# STM32Headers.net
KiCad netlist of a schematic drawn in Altium Designer
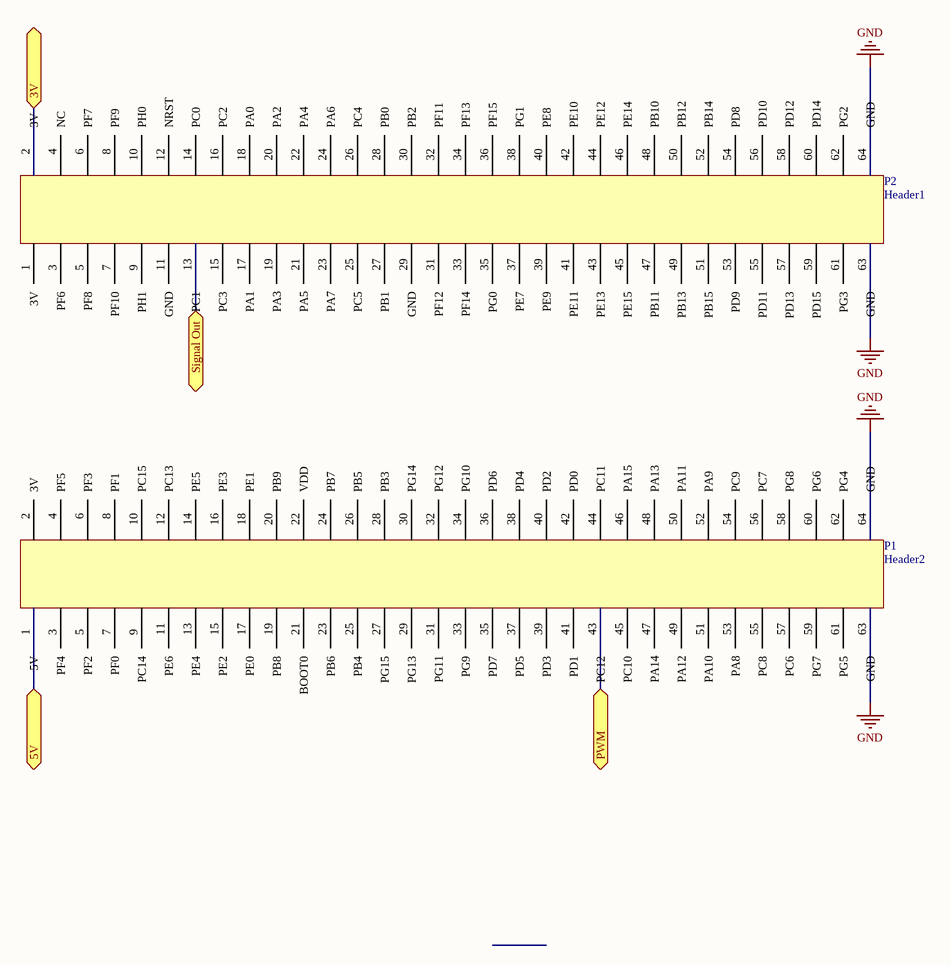
[diagram p0: STM32Headers.SchDoc]

(export (version "E")
  (design (tool "Eeschema 10.0.6"))
  (components
    (comp (ref "P1")
      (value "Header2")
      (footprint "STM32F4DiscoHeader")
      (libsource (lib "STM32F4DISCOHEAD2") (part "Component_1"))
    )
    (comp (ref "P2")
      (value "Header1")
      (footprint "STM32F4DiscoHeader")
      (description "Header for STM32F429 pinout")
      (libsource (lib "STM32F4DISCOHEAD") (part "Component_1"))
    )
  )
  (nets
    (net (code "1") (name "/3V") (class "Default")
      (node (ref "P2") (pin "2") (pinfunction "3V_2") (pintype "power_in"))
    )
    (net (code "2") (name "/5V") (class "Default")
      (node (ref "P1") (pin "1") (pinfunction "5V_1") (pintype "power_in"))
    )
    (net (code "3") (name "/PWM") (class "Default")
      (node (ref "P1") (pin "43") (pinfunction "PC12_43") (pintype "passive"))
    )
    (net (code "4") (name "/Signal Out") (class "Default")
      (node (ref "P2") (pin "13") (pinfunction "PC1_13") (pintype "passive"))
    )
    (net (code "5") (name "GND") (class "Default")
      (node (ref "P1") (pin "63") (pinfunction "GND_63") (pintype "power_in"))
      (node (ref "P1") (pin "64") (pinfunction "GND_64") (pintype "power_in"))
      (node (ref "P2") (pin "63") (pinfunction "GND_63") (pintype "power_in"))
      (node (ref "P2") (pin "64") (pinfunction "GND_64") (pintype "power_in"))
    )
    (net (code "6") (name "unconnected-(P1-3V-Pad2)") (class "Default")
      (node (ref "P1") (pin "2") (pinfunction "3V_2") (pintype "power_in"))
    )
    (net (code "7") (name "unconnected-(P1-BOOT0-Pad21)") (class "Default")
      (node (ref "P1") (pin "21") (pinfunction "BOOT0_21") (pintype "passive"))
    )
    (net (code "8") (name "unconnected-(P1-PA8-Pad53)") (class "Default")
      (node (ref "P1") (pin "53") (pinfunction "PA8_53") (pintype "passive"))
    )
    (net (code "9") (name "unconnected-(P1-PA9-Pad52)") (class "Default")
      (node (ref "P1") (pin "52") (pinfunction "PA9_52") (pintype "passive"))
    )
    (net (code "10") (name "unconnected-(P1-PA10-Pad51)") (class "Default")
      (node (ref "P1") (pin "51") (pinfunction "PA10_51") (pintype "passive"))
    )
    (net (code "11") (name "unconnected-(P1-PA11-Pad50)") (class "Default")
      (node (ref "P1") (pin "50") (pinfunction "PA11_50") (pintype "passive"))
    )
    (net (code "12") (name "unconnected-(P1-PA12-Pad49)") (class "Default")
      (node (ref "P1") (pin "49") (pinfunction "PA12_49") (pintype "passive"))
    )
    (net (code "13") (name "unconnected-(P1-PA13-Pad48)") (class "Default")
      (node (ref "P1") (pin "48") (pinfunction "PA13_48") (pintype "passive"))
    )
    (net (code "14") (name "unconnected-(P1-PA14-Pad47)") (class "Default")
      (node (ref "P1") (pin "47") (pinfunction "PA14_47") (pintype "passive"))
    )
    (net (code "15") (name "unconnected-(P1-PA15-Pad46)") (class "Default")
      (node (ref "P1") (pin "46") (pinfunction "PA15_46") (pintype "passive"))
    )
    (net (code "16") (name "unconnected-(P1-PB3-Pad28)") (class "Default")
      (node (ref "P1") (pin "28") (pinfunction "PB3_28") (pintype "passive"))
    )
    (net (code "17") (name "unconnected-(P1-PB4-Pad25)") (class "Default")
      (node (ref "P1") (pin "25") (pinfunction "PB4_25") (pintype "passive"))
    )
    (net (code "18") (name "unconnected-(P1-PB5-Pad26)") (class "Default")
      (node (ref "P1") (pin "26") (pinfunction "PB5_26") (pintype "passive"))
    )
    (net (code "19") (name "unconnected-(P1-PB6-Pad23)") (class "Default")
      (node (ref "P1") (pin "23") (pinfunction "PB6_23") (pintype "passive"))
    )
    (net (code "20") (name "unconnected-(P1-PB7-Pad24)") (class "Default")
      (node (ref "P1") (pin "24") (pinfunction "PB7_24") (pintype "passive"))
    )
    (net (code "21") (name "unconnected-(P1-PB8-Pad19)") (class "Default")
      (node (ref "P1") (pin "19") (pinfunction "PB8_19") (pintype "passive"))
    )
    (net (code "22") (name "unconnected-(P1-PB9-Pad20)") (class "Default")
      (node (ref "P1") (pin "20") (pinfunction "PB9_20") (pintype "passive"))
    )
    (net (code "23") (name "unconnected-(P1-PC6-Pad57)") (class "Default")
      (node (ref "P1") (pin "57") (pinfunction "PC6_57") (pintype "passive"))
    )
    (net (code "24") (name "unconnected-(P1-PC7-Pad56)") (class "Default")
      (node (ref "P1") (pin "56") (pinfunction "PC7_56") (pintype "passive"))
    )
    (net (code "25") (name "unconnected-(P1-PC8-Pad55)") (class "Default")
      (node (ref "P1") (pin "55") (pinfunction "PC8_55") (pintype "passive"))
    )
    (net (code "26") (name "unconnected-(P1-PC9-Pad54)") (class "Default")
      (node (ref "P1") (pin "54") (pinfunction "PC9_54") (pintype "passive"))
    )
    (net (code "27") (name "unconnected-(P1-PC10-Pad45)") (class "Default")
      (node (ref "P1") (pin "45") (pinfunction "PC10_45") (pintype "passive"))
    )
    (net (code "28") (name "unconnected-(P1-PC11-Pad44)") (class "Default")
      (node (ref "P1") (pin "44") (pinfunction "PC11_44") (pintype "passive"))
    )
    (net (code "29") (name "unconnected-(P1-PC13-Pad12)") (class "Default")
      (node (ref "P1") (pin "12") (pinfunction "PC13_12") (pintype "passive"))
    )
    (net (code "30") (name "unconnected-(P1-PC14-Pad9)") (class "Default")
      (node (ref "P1") (pin "9") (pinfunction "PC14_9") (pintype "passive"))
    )
    (net (code "31") (name "unconnected-(P1-PC15-Pad10)") (class "Default")
      (node (ref "P1") (pin "10") (pinfunction "PC15_10") (pintype "passive"))
    )
    (net (code "32") (name "unconnected-(P1-PD0-Pad42)") (class "Default")
      (node (ref "P1") (pin "42") (pinfunction "PD0_42") (pintype "passive"))
    )
    (net (code "33") (name "unconnected-(P1-PD1-Pad41)") (class "Default")
      (node (ref "P1") (pin "41") (pinfunction "PD1_41") (pintype "passive"))
    )
    (net (code "34") (name "unconnected-(P1-PD2-Pad40)") (class "Default")
      (node (ref "P1") (pin "40") (pinfunction "PD2_40") (pintype "passive"))
    )
    (net (code "35") (name "unconnected-(P1-PD3-Pad39)") (class "Default")
      (node (ref "P1") (pin "39") (pinfunction "PD3_39") (pintype "passive"))
    )
    (net (code "36") (name "unconnected-(P1-PD4-Pad38)") (class "Default")
      (node (ref "P1") (pin "38") (pinfunction "PD4_38") (pintype "passive"))
    )
    (net (code "37") (name "unconnected-(P1-PD5-Pad37)") (class "Default")
      (node (ref "P1") (pin "37") (pinfunction "PD5_37") (pintype "passive"))
    )
    (net (code "38") (name "unconnected-(P1-PD6-Pad36)") (class "Default")
      (node (ref "P1") (pin "36") (pinfunction "PD6_36") (pintype "passive"))
    )
    (net (code "39") (name "unconnected-(P1-PD7-Pad35)") (class "Default")
      (node (ref "P1") (pin "35") (pinfunction "PD7_35") (pintype "passive"))
    )
    (net (code "40") (name "unconnected-(P1-PE0-Pad17)") (class "Default")
      (node (ref "P1") (pin "17") (pinfunction "PE0_17") (pintype "passive"))
    )
    (net (code "41") (name "unconnected-(P1-PE1-Pad18)") (class "Default")
      (node (ref "P1") (pin "18") (pinfunction "PE1_18") (pintype "passive"))
    )
    (net (code "42") (name "unconnected-(P1-PE2-Pad15)") (class "Default")
      (node (ref "P1") (pin "15") (pinfunction "PE2_15") (pintype "passive"))
    )
    (net (code "43") (name "unconnected-(P1-PE3-Pad16)") (class "Default")
      (node (ref "P1") (pin "16") (pinfunction "PE3_16") (pintype "passive"))
    )
    (net (code "44") (name "unconnected-(P1-PE4-Pad13)") (class "Default")
      (node (ref "P1") (pin "13") (pinfunction "PE4_13") (pintype "passive"))
    )
    (net (code "45") (name "unconnected-(P1-PE5-Pad14)") (class "Default")
      (node (ref "P1") (pin "14") (pinfunction "PE5_14") (pintype "passive"))
    )
    (net (code "46") (name "unconnected-(P1-PE6-Pad11)") (class "Default")
      (node (ref "P1") (pin "11") (pinfunction "PE6_11") (pintype "passive"))
    )
    (net (code "47") (name "unconnected-(P1-PF0-Pad7)") (class "Default")
      (node (ref "P1") (pin "7") (pinfunction "PF0_7") (pintype "passive"))
    )
    (net (code "48") (name "unconnected-(P1-PF1-Pad8)") (class "Default")
      (node (ref "P1") (pin "8") (pinfunction "PF1_8") (pintype "passive"))
    )
    (net (code "49") (name "unconnected-(P1-PF2-Pad5)") (class "Default")
      (node (ref "P1") (pin "5") (pinfunction "PF2_5") (pintype "passive"))
    )
    (net (code "50") (name "unconnected-(P1-PF3-Pad6)") (class "Default")
      (node (ref "P1") (pin "6") (pinfunction "PF3_6") (pintype "passive"))
    )
    (net (code "51") (name "unconnected-(P1-PF4-Pad3)") (class "Default")
      (node (ref "P1") (pin "3") (pinfunction "PF4_3") (pintype "passive"))
    )
    (net (code "52") (name "unconnected-(P1-PF5-Pad4)") (class "Default")
      (node (ref "P1") (pin "4") (pinfunction "PF5_4") (pintype "passive"))
    )
    (net (code "53") (name "unconnected-(P1-PG4-Pad62)") (class "Default")
      (node (ref "P1") (pin "62") (pinfunction "PG4_62") (pintype "passive"))
    )
    (net (code "54") (name "unconnected-(P1-PG5-Pad61)") (class "Default")
      (node (ref "P1") (pin "61") (pinfunction "PG5_61") (pintype "passive"))
    )
    (net (code "55") (name "unconnected-(P1-PG6-Pad60)") (class "Default")
      (node (ref "P1") (pin "60") (pinfunction "PG6_60") (pintype "passive"))
    )
    (net (code "56") (name "unconnected-(P1-PG7-Pad59)") (class "Default")
      (node (ref "P1") (pin "59") (pinfunction "PG7_59") (pintype "passive"))
    )
    (net (code "57") (name "unconnected-(P1-PG8-Pad58)") (class "Default")
      (node (ref "P1") (pin "58") (pinfunction "PG8_58") (pintype "passive"))
    )
    (net (code "58") (name "unconnected-(P1-PG9-Pad33)") (class "Default")
      (node (ref "P1") (pin "33") (pinfunction "PG9_33") (pintype "passive"))
    )
    (net (code "59") (name "unconnected-(P1-PG10-Pad34)") (class "Default")
      (node (ref "P1") (pin "34") (pinfunction "PG10_34") (pintype "passive"))
    )
    (net (code "60") (name "unconnected-(P1-PG11-Pad31)") (class "Default")
      (node (ref "P1") (pin "31") (pinfunction "PG11_31") (pintype "passive"))
    )
    (net (code "61") (name "unconnected-(P1-PG12-Pad32)") (class "Default")
      (node (ref "P1") (pin "32") (pinfunction "PG12_32") (pintype "passive"))
    )
    (net (code "62") (name "unconnected-(P1-PG13-Pad29)") (class "Default")
      (node (ref "P1") (pin "29") (pinfunction "PG13_29") (pintype "passive"))
    )
    (net (code "63") (name "unconnected-(P1-PG14-Pad30)") (class "Default")
      (node (ref "P1") (pin "30") (pinfunction "PG14_30") (pintype "passive"))
    )
    (net (code "64") (name "unconnected-(P1-PG15-Pad27)") (class "Default")
      (node (ref "P1") (pin "27") (pinfunction "PG15_27") (pintype "passive"))
    )
    (net (code "65") (name "unconnected-(P1-VDD-Pad22)") (class "Default")
      (node (ref "P1") (pin "22") (pinfunction "VDD_22") (pintype "power_in"))
    )
    (net (code "66") (name "unconnected-(P2-3V-Pad1)") (class "Default")
      (node (ref "P2") (pin "1") (pinfunction "3V_1") (pintype "power_in"))
    )
    (net (code "67") (name "unconnected-(P2-GND-Pad11)") (class "Default")
      (node (ref "P2") (pin "11") (pinfunction "GND_11") (pintype "power_in"))
    )
    (net (code "68") (name "unconnected-(P2-GND-Pad29)") (class "Default")
      (node (ref "P2") (pin "29") (pinfunction "GND_29") (pintype "power_in"))
    )
    (net (code "69") (name "unconnected-(P2-NC-Pad4)") (class "Default")
      (node (ref "P2") (pin "4") (pinfunction "NC_4") (pintype "passive"))
    )
    (net (code "70") (name "unconnected-(P2-NRST-Pad12)") (class "Default")
      (node (ref "P2") (pin "12") (pinfunction "NRST_12") (pintype "passive"))
    )
    (net (code "71") (name "unconnected-(P2-PA0-Pad18)") (class "Default")
      (node (ref "P2") (pin "18") (pinfunction "PA0_18") (pintype "passive"))
    )
    (net (code "72") (name "unconnected-(P2-PA1-Pad17)") (class "Default")
      (node (ref "P2") (pin "17") (pinfunction "PA1_17") (pintype "passive"))
    )
    (net (code "73") (name "unconnected-(P2-PA2-Pad20)") (class "Default")
      (node (ref "P2") (pin "20") (pinfunction "PA2_20") (pintype "passive"))
    )
    (net (code "74") (name "unconnected-(P2-PA3-Pad19)") (class "Default")
      (node (ref "P2") (pin "19") (pinfunction "PA3_19") (pintype "passive"))
    )
    (net (code "75") (name "unconnected-(P2-PA4-Pad22)") (class "Default")
      (node (ref "P2") (pin "22") (pinfunction "PA4_22") (pintype "passive"))
    )
    (net (code "76") (name "unconnected-(P2-PA5-Pad21)") (class "Default")
      (node (ref "P2") (pin "21") (pinfunction "PA5_21") (pintype "passive"))
    )
    (net (code "77") (name "unconnected-(P2-PA6-Pad24)") (class "Default")
      (node (ref "P2") (pin "24") (pinfunction "PA6_24") (pintype "passive"))
    )
    (net (code "78") (name "unconnected-(P2-PA7-Pad23)") (class "Default")
      (node (ref "P2") (pin "23") (pinfunction "PA7_23") (pintype "passive"))
    )
    (net (code "79") (name "unconnected-(P2-PB0-Pad28)") (class "Default")
      (node (ref "P2") (pin "28") (pinfunction "PB0_28") (pintype "passive"))
    )
    (net (code "80") (name "unconnected-(P2-PB1-Pad27)") (class "Default")
      (node (ref "P2") (pin "27") (pinfunction "PB1_27") (pintype "passive"))
    )
    (net (code "81") (name "unconnected-(P2-PB2-Pad30)") (class "Default")
      (node (ref "P2") (pin "30") (pinfunction "PB2_30") (pintype "passive"))
    )
    (net (code "82") (name "unconnected-(P2-PB10-Pad48)") (class "Default")
      (node (ref "P2") (pin "48") (pinfunction "PB10_48") (pintype "passive"))
    )
    (net (code "83") (name "unconnected-(P2-PB11-Pad47)") (class "Default")
      (node (ref "P2") (pin "47") (pinfunction "PB11_47") (pintype "passive"))
    )
    (net (code "84") (name "unconnected-(P2-PB12-Pad50)") (class "Default")
      (node (ref "P2") (pin "50") (pinfunction "PB12_50") (pintype "passive"))
    )
    (net (code "85") (name "unconnected-(P2-PB13-Pad49)") (class "Default")
      (node (ref "P2") (pin "49") (pinfunction "PB13_49") (pintype "passive"))
    )
    (net (code "86") (name "unconnected-(P2-PB14-Pad52)") (class "Default")
      (node (ref "P2") (pin "52") (pinfunction "PB14_52") (pintype "passive"))
    )
    (net (code "87") (name "unconnected-(P2-PB15-Pad51)") (class "Default")
      (node (ref "P2") (pin "51") (pinfunction "PB15_51") (pintype "passive"))
    )
    (net (code "88") (name "unconnected-(P2-PC0-Pad14)") (class "Default")
      (node (ref "P2") (pin "14") (pinfunction "PC0_14") (pintype "passive"))
    )
    (net (code "89") (name "unconnected-(P2-PC2-Pad16)") (class "Default")
      (node (ref "P2") (pin "16") (pinfunction "PC2_16") (pintype "passive"))
    )
    (net (code "90") (name "unconnected-(P2-PC3-Pad15)") (class "Default")
      (node (ref "P2") (pin "15") (pinfunction "PC3_15") (pintype "passive"))
    )
    (net (code "91") (name "unconnected-(P2-PC4-Pad26)") (class "Default")
      (node (ref "P2") (pin "26") (pinfunction "PC4_26") (pintype "passive"))
    )
    (net (code "92") (name "unconnected-(P2-PC5-Pad25)") (class "Default")
      (node (ref "P2") (pin "25") (pinfunction "PC5_25") (pintype "passive"))
    )
    (net (code "93") (name "unconnected-(P2-PD8-Pad54)") (class "Default")
      (node (ref "P2") (pin "54") (pinfunction "PD8_54") (pintype "passive"))
    )
    (net (code "94") (name "unconnected-(P2-PD9-Pad53)") (class "Default")
      (node (ref "P2") (pin "53") (pinfunction "PD9_53") (pintype "passive"))
    )
    (net (code "95") (name "unconnected-(P2-PD10-Pad56)") (class "Default")
      (node (ref "P2") (pin "56") (pinfunction "PD10_56") (pintype "passive"))
    )
    (net (code "96") (name "unconnected-(P2-PD11-Pad55)") (class "Default")
      (node (ref "P2") (pin "55") (pinfunction "PD11_55") (pintype "passive"))
    )
    (net (code "97") (name "unconnected-(P2-PD12-Pad58)") (class "Default")
      (node (ref "P2") (pin "58") (pinfunction "PD12_58") (pintype "passive"))
    )
    (net (code "98") (name "unconnected-(P2-PD13-Pad57)") (class "Default")
      (node (ref "P2") (pin "57") (pinfunction "PD13_57") (pintype "passive"))
    )
    (net (code "99") (name "unconnected-(P2-PD14-Pad60)") (class "Default")
      (node (ref "P2") (pin "60") (pinfunction "PD14_60") (pintype "passive"))
    )
    (net (code "100") (name "unconnected-(P2-PD15-Pad59)") (class "Default")
      (node (ref "P2") (pin "59") (pinfunction "PD15_59") (pintype "passive"))
    )
    (net (code "101") (name "unconnected-(P2-PE7-Pad37)") (class "Default")
      (node (ref "P2") (pin "37") (pinfunction "PE7_37") (pintype "passive"))
    )
    (net (code "102") (name "unconnected-(P2-PE8-Pad40)") (class "Default")
      (node (ref "P2") (pin "40") (pinfunction "PE8_40") (pintype "passive"))
    )
    (net (code "103") (name "unconnected-(P2-PE9-Pad39)") (class "Default")
      (node (ref "P2") (pin "39") (pinfunction "PE9_39") (pintype "passive"))
    )
    (net (code "104") (name "unconnected-(P2-PE10-Pad42)") (class "Default")
      (node (ref "P2") (pin "42") (pinfunction "PE10_42") (pintype "passive"))
    )
    (net (code "105") (name "unconnected-(P2-PE11-Pad41)") (class "Default")
      (node (ref "P2") (pin "41") (pinfunction "PE11_41") (pintype "passive"))
    )
    (net (code "106") (name "unconnected-(P2-PE12-Pad44)") (class "Default")
      (node (ref "P2") (pin "44") (pinfunction "PE12_44") (pintype "passive"))
    )
    (net (code "107") (name "unconnected-(P2-PE13-Pad43)") (class "Default")
      (node (ref "P2") (pin "43") (pinfunction "PE13_43") (pintype "passive"))
    )
    (net (code "108") (name "unconnected-(P2-PE14-Pad46)") (class "Default")
      (node (ref "P2") (pin "46") (pinfunction "PE14_46") (pintype "passive"))
    )
    (net (code "109") (name "unconnected-(P2-PE15-Pad45)") (class "Default")
      (node (ref "P2") (pin "45") (pinfunction "PE15_45") (pintype "passive"))
    )
    (net (code "110") (name "unconnected-(P2-PF6-Pad3)") (class "Default")
      (node (ref "P2") (pin "3") (pinfunction "PF6_3") (pintype "passive"))
    )
    (net (code "111") (name "unconnected-(P2-PF7-Pad6)") (class "Default")
      (node (ref "P2") (pin "6") (pinfunction "PF7_6") (pintype "passive"))
    )
    (net (code "112") (name "unconnected-(P2-PF8-Pad5)") (class "Default")
      (node (ref "P2") (pin "5") (pinfunction "PF8_5") (pintype "passive"))
    )
    (net (code "113") (name "unconnected-(P2-PF9-Pad8)") (class "Default")
      (node (ref "P2") (pin "8") (pinfunction "PF9_8") (pintype "passive"))
    )
    (net (code "114") (name "unconnected-(P2-PF10-Pad7)") (class "Default")
      (node (ref "P2") (pin "7") (pinfunction "PF10_7") (pintype "passive"))
    )
    (net (code "115") (name "unconnected-(P2-PF11-Pad32)") (class "Default")
      (node (ref "P2") (pin "32") (pinfunction "PF11_32") (pintype "passive"))
    )
    (net (code "116") (name "unconnected-(P2-PF12-Pad31)") (class "Default")
      (node (ref "P2") (pin "31") (pinfunction "PF12_31") (pintype "passive"))
    )
    (net (code "117") (name "unconnected-(P2-PF13-Pad34)") (class "Default")
      (node (ref "P2") (pin "34") (pinfunction "PF13_34") (pintype "passive"))
    )
    (net (code "118") (name "unconnected-(P2-PF14-Pad33)") (class "Default")
      (node (ref "P2") (pin "33") (pinfunction "PF14_33") (pintype "passive"))
    )
    (net (code "119") (name "unconnected-(P2-PF15-Pad36)") (class "Default")
      (node (ref "P2") (pin "36") (pinfunction "PF15_36") (pintype "passive"))
    )
    (net (code "120") (name "unconnected-(P2-PG0-Pad35)") (class "Default")
      (node (ref "P2") (pin "35") (pinfunction "PG0_35") (pintype "passive"))
    )
    (net (code "121") (name "unconnected-(P2-PG1-Pad38)") (class "Default")
      (node (ref "P2") (pin "38") (pinfunction "PG1_38") (pintype "passive"))
    )
    (net (code "122") (name "unconnected-(P2-PG2-Pad62)") (class "Default")
      (node (ref "P2") (pin "62") (pinfunction "PG2_62") (pintype "passive"))
    )
    (net (code "123") (name "unconnected-(P2-PG3-Pad61)") (class "Default")
      (node (ref "P2") (pin "61") (pinfunction "PG3_61") (pintype "passive"))
    )
    (net (code "124") (name "unconnected-(P2-PH0-Pad10)") (class "Default")
      (node (ref "P2") (pin "10") (pinfunction "PH0_10") (pintype "passive"))
    )
    (net (code "125") (name "unconnected-(P2-PH1-Pad9)") (class "Default")
      (node (ref "P2") (pin "9") (pinfunction "PH1_9") (pintype "passive"))
    )
  )
)
